# tetris_big_noregulator.net
KiCad netlist of a schematic drawn in EAGLE
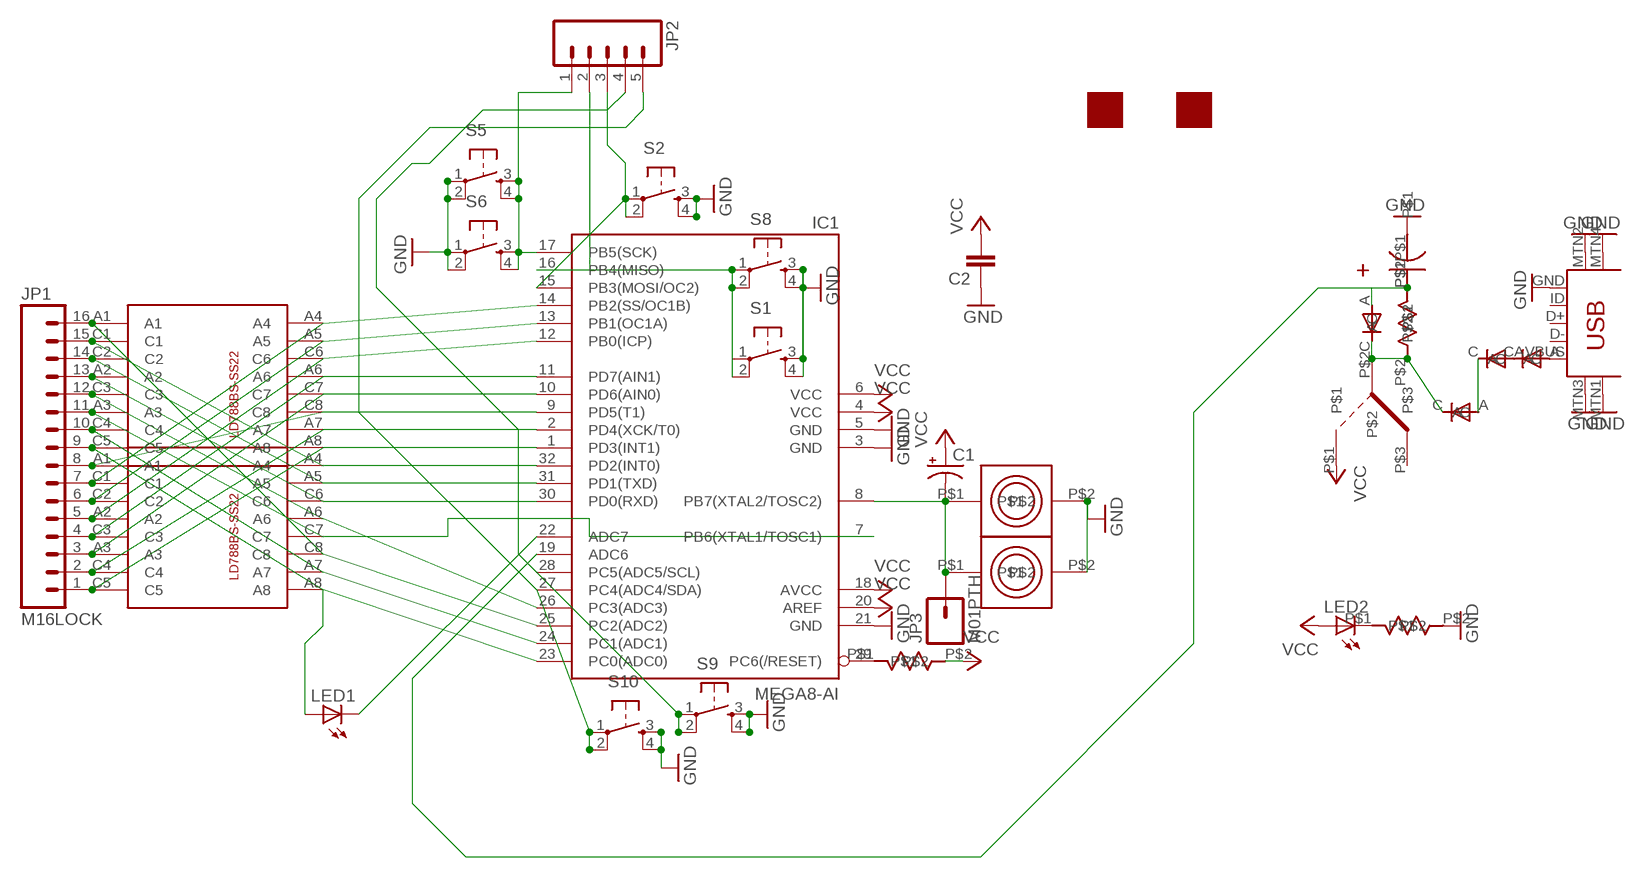
[diagram p0: schematic, sheet 1]

(export (version "E")
  (design (tool "Eeschema 10.0.6"))
  (components
    (comp (ref "C1")
      (value "CAP_POLPTH1")
      (footprint "eagle-import:CPOL-RADIAL-100UF-25V")
      (libsource (lib "eagle-import") (part "CAP_POLPTH1"))
    )
    (comp (ref "C2")
      (value "C-EU025-025X050")
      (footprint "eagle-import:C025-025X050")
      (libsource (lib "eagle-import") (part "C-EU025-025X050"))
    )
    (comp (ref "IC1")
      (value "MEGA8-AI")
      (footprint "eagle-import:TQFP32-08")
      (fields
        (field (name "MPN") "ATMEGA8-16AU")
        (field (name "MPN_1") "ATMEGA8-16AU")
        (field (name "OC_FARNELL") "9171371")
        (field (name "OC_NEWARK") "73M8863")
      )
      (libsource (lib "eagle-import") (part "MEGA8-AI"))
    )
    (comp (ref "JP1")
      (value "M16LOCK")
      (footprint "eagle-import:1X16_LOCK")
      (libsource (lib "eagle-import") (part "M16LOCK"))
    )
    (comp (ref "JP2")
      (value "M05LOCK")
      (footprint "eagle-import:1X05_LOCK")
      (libsource (lib "eagle-import") (part "M05LOCK"))
    )
    (comp (ref "JP3")
      (value "M01PTH")
      (footprint "eagle-import:1X01")
      (libsource (lib "eagle-import") (part "M01PTH"))
    )
    (comp (ref "LED1")
      (value "LED3MM")
      (footprint "eagle-import:LED3MM")
      (libsource (lib "eagle-import") (part "LED3MM"))
    )
    (comp (ref "LED2")
      (value "LED3MM")
      (footprint "eagle-import:LED3MM")
      (libsource (lib "eagle-import") (part "LED3MM"))
    )
    (comp (ref "S1")
      (value "TAC_SWITCHPTH")
      (footprint "eagle-import:TACTILE-PTH")
      (libsource (lib "eagle-import") (part "TAC_SWITCHPTH"))
    )
    (comp (ref "S2")
      (value "TAC_SWITCHPTH")
      (footprint "eagle-import:TACTILE-PTH")
      (libsource (lib "eagle-import") (part "TAC_SWITCHPTH"))
    )
    (comp (ref "S5")
      (value "TAC_SWITCHPTH")
      (footprint "eagle-import:TACTILE-PTH")
      (libsource (lib "eagle-import") (part "TAC_SWITCHPTH"))
    )
    (comp (ref "S6")
      (value "TAC_SWITCHPTH")
      (footprint "eagle-import:TACTILE-PTH")
      (libsource (lib "eagle-import") (part "TAC_SWITCHPTH"))
    )
    (comp (ref "S8")
      (value "TAC_SWITCHPTH")
      (footprint "eagle-import:TACTILE-PTH")
      (libsource (lib "eagle-import") (part "TAC_SWITCHPTH"))
    )
    (comp (ref "S9")
      (value "TAC_SWITCHPTH")
      (footprint "eagle-import:TACTILE-PTH")
      (libsource (lib "eagle-import") (part "TAC_SWITCHPTH"))
    )
    (comp (ref "S10")
      (value "TAC_SWITCHPTH")
      (footprint "eagle-import:TACTILE-PTH")
      (libsource (lib "eagle-import") (part "TAC_SWITCHPTH"))
    )
    (comp (ref "U$1")
      (value "LD-1088BS")
      (footprint "eagle-import:LD-1088BS")
      (libsource (lib "eagle-import") (part "LD-1088BS"))
    )
    (comp (ref "U$2")
      (value "LD-1088BS")
      (footprint "eagle-import:LD-1088BS")
      (libsource (lib "eagle-import") (part "LD-1088BS"))
    )
    (comp (ref "U$3")
      (value "LOGO")
      (footprint "eagle-import:LOGO")
      (libsource (lib "eagle-import") (part "LOGO"))
    )
    (comp (ref "U$4")
      (value "I-80450RF")
      (footprint "eagle-import:ISK4.1K_I-80450RF_I2G")
      (libsource (lib "eagle-import") (part "I-80450RF"))
    )
    (comp (ref "U$5")
      (value "NICHICON_12F")
      (footprint "eagle-import:NICHICON_10X30")
      (libsource (lib "eagle-import") (part "NICHICON_12F"))
    )
    (comp (ref "U$6")
      (value "LOGO")
      (footprint "eagle-import:LOGO")
      (libsource (lib "eagle-import") (part "LOGO"))
    )
    (comp (ref "U$7")
      (value "PIEZO_ROUND_PTH")
      (footprint "eagle-import:PIEZO_ROUND_ENCASED_PTH")
      (libsource (lib "eagle-import") (part "PIEZO_ROUND_PTH"))
    )
    (comp (ref "U$8")
      (value "R-7")
      (footprint "eagle-import:R-7")
      (libsource (lib "eagle-import") (part "R-7"))
    )
    (comp (ref "U$9")
      (value "SPST_BIG_PTH")
      (footprint "eagle-import:SWITCH_BIG")
      (libsource (lib "eagle-import") (part "SPST_BIG_PTH"))
    )
    (comp (ref "U$10")
      (value "R-7")
      (footprint "eagle-import:R-7")
      (libsource (lib "eagle-import") (part "R-7"))
    )
    (comp (ref "U$11")
      (value "R-7")
      (footprint "eagle-import:R-7")
      (libsource (lib "eagle-import") (part "R-7"))
    )
    (comp (ref "U$13")
      (value "D-6")
      (footprint "eagle-import:D-7.5")
      (libsource (lib "eagle-import") (part "D-6"))
    )
    (comp (ref "U$14")
      (value "D-6")
      (footprint "eagle-import:D-7.5")
      (libsource (lib "eagle-import") (part "D-6"))
    )
    (comp (ref "U$15")
      (value "D-6")
      (footprint "eagle-import:D-7.5")
      (libsource (lib "eagle-import") (part "D-6"))
    )
    (comp (ref "U$16")
      (value "D-6")
      (footprint "eagle-import:D-7.5")
      (libsource (lib "eagle-import") (part "D-6"))
    )
    (comp (ref "X1")
      (value "USB-MINIB-5PIN")
      (footprint "eagle-import:USB-MINIB")
      (libsource (lib "eagle-import") (part "USB-MINIB-5PIN"))
    )
  )
  (nets
    (net (code "1") (name "GND") (class "Default")
      (node (ref "C2") (pin "1") (pinfunction "1_1") (pintype "passive"))
      (node (ref "IC1") (pin "21") (pinfunction "GND_21") (pintype "power_in"))
      (node (ref "IC1") (pin "3") (pinfunction "GND_3") (pintype "power_in"))
      (node (ref "IC1") (pin "5") (pinfunction "GND_5") (pintype "power_in"))
      (node (ref "S1") (pin "3") (pinfunction "3_3") (pintype "passive"))
      (node (ref "S1") (pin "4") (pinfunction "4_4") (pintype "passive"))
      (node (ref "S10") (pin "3") (pinfunction "3_3") (pintype "passive"))
      (node (ref "S10") (pin "4") (pinfunction "4_4") (pintype "passive"))
      (node (ref "S2") (pin "3") (pinfunction "3_3") (pintype "passive"))
      (node (ref "S2") (pin "4") (pinfunction "4_4") (pintype "passive"))
      (node (ref "S5") (pin "1") (pinfunction "1_1") (pintype "passive"))
      (node (ref "S5") (pin "2") (pinfunction "2_2") (pintype "passive"))
      (node (ref "S6") (pin "1") (pinfunction "1_1") (pintype "passive"))
      (node (ref "S6") (pin "2") (pinfunction "2_2") (pintype "passive"))
      (node (ref "S8") (pin "3") (pinfunction "3_3") (pintype "passive"))
      (node (ref "S8") (pin "4") (pinfunction "4_4") (pintype "passive"))
      (node (ref "S9") (pin "3") (pinfunction "3_3") (pintype "passive"))
      (node (ref "S9") (pin "4") (pinfunction "4_4") (pintype "passive"))
      (node (ref "U$11") (pin "P$2") (pinfunction "P$2_P$2") (pintype "bidirectional"))
      (node (ref "U$4") (pin "P$2") (pinfunction "P$2_P$2") (pintype "bidirectional"))
      (node (ref "U$5") (pin "P$1") (pinfunction "P$1_P$1") (pintype "bidirectional"))
      (node (ref "U$7") (pin "P$2") (pinfunction "P$2_P$2") (pintype "bidirectional"))
      (node (ref "X1") (pin "GND") (pinfunction "GND_GND") (pintype "bidirectional"))
      (node (ref "X1") (pin "MTN1") (pinfunction "MTN2_MTN1") (pintype "bidirectional"))
      (node (ref "X1") (pin "MTN2") (pinfunction "MTN3_MTN2") (pintype "bidirectional"))
      (node (ref "X1") (pin "MTN3") (pinfunction "MTN1_MTN3") (pintype "bidirectional"))
      (node (ref "X1") (pin "MTN4") (pinfunction "MTN4_MTN4") (pintype "bidirectional"))
    )
    (net (code "2") (name "Net-(C1--)") (class "Default")
      (node (ref "C1") (pin "2") (pinfunction "-_2") (pintype "passive"))
      (node (ref "IC1") (pin "8") (pinfunction "PB7(XTAL2/TOSC2)_8") (pintype "bidirectional"))
      (node (ref "JP3") (pin "1") (pinfunction "1_1") (pintype "passive"))
      (node (ref "U$4") (pin "P$1") (pinfunction "P$1_P$1") (pintype "bidirectional"))
      (node (ref "U$7") (pin "P$1") (pinfunction "P$1_P$1") (pintype "bidirectional"))
    )
    (net (code "3") (name "Net-(IC1-ADC6)") (class "Default")
      (node (ref "IC1") (pin "19") (pinfunction "ADC6_19") (pintype "bidirectional"))
      (node (ref "U$16") (pin "A") (pinfunction "A_A") (pintype "bidirectional"))
      (node (ref "U$5") (pin "P$2") (pinfunction "P$2_P$2") (pintype "bidirectional"))
      (node (ref "U$8") (pin "P$1") (pinfunction "P$1_P$1") (pintype "bidirectional"))
    )
    (net (code "4") (name "Net-(IC1-ADC7)") (class "Default")
      (node (ref "IC1") (pin "22") (pinfunction "ADC7_22") (pintype "bidirectional"))
      (node (ref "LED1") (pin "K") (pinfunction "C_K") (pintype "passive"))
    )
    (net (code "5") (name "Net-(IC1-PB0(ICP))") (class "Default")
      (node (ref "IC1") (pin "12") (pinfunction "PB0(ICP)_12") (pintype "bidirectional"))
      (node (ref "JP1") (pin "5") (pinfunction "5_5") (pintype "passive"))
      (node (ref "U$1") (pin "A2") (pinfunction "A2_A2") (pintype "bidirectional"))
      (node (ref "U$2") (pin "C6") (pinfunction "C6_C6") (pintype "bidirectional"))
    )
    (net (code "6") (name "Net-(IC1-PB1(OC1A))") (class "Default")
      (node (ref "IC1") (pin "13") (pinfunction "PB1(OC1A)_13") (pintype "bidirectional"))
      (node (ref "JP1") (pin "6") (pinfunction "6_6") (pintype "passive"))
      (node (ref "U$1") (pin "C2") (pinfunction "C2_C2") (pintype "bidirectional"))
      (node (ref "U$2") (pin "A5") (pinfunction "A5_A5") (pintype "bidirectional"))
    )
    (net (code "7") (name "Net-(IC1-PB2(SS{slash}OC1B))") (class "Default")
      (node (ref "IC1") (pin "14") (pinfunction "PB2(SS/OC1B)_14") (pintype "bidirectional"))
      (node (ref "JP1") (pin "7") (pinfunction "7_7") (pintype "passive"))
      (node (ref "U$1") (pin "C1") (pinfunction "C1_C1") (pintype "bidirectional"))
      (node (ref "U$2") (pin "A4") (pinfunction "A4_A4") (pintype "bidirectional"))
    )
    (net (code "8") (name "Net-(IC1-PB3(MOSI{slash}OC2))") (class "Default")
      (node (ref "IC1") (pin "15") (pinfunction "PB3(MOSI/OC2)_15") (pintype "bidirectional"))
      (node (ref "JP2") (pin "3") (pinfunction "3_3") (pintype "passive"))
      (node (ref "S2") (pin "1") (pinfunction "1_1") (pintype "passive"))
      (node (ref "S2") (pin "2") (pinfunction "2_2") (pintype "passive"))
    )
    (net (code "9") (name "Net-(IC1-PB4(MISO))") (class "Default")
      (node (ref "IC1") (pin "16") (pinfunction "PB4(MISO)_16") (pintype "bidirectional"))
      (node (ref "JP2") (pin "2") (pinfunction "2_2") (pintype "passive"))
      (node (ref "S1") (pin "1") (pinfunction "1_1") (pintype "passive"))
      (node (ref "S1") (pin "2") (pinfunction "2_2") (pintype "passive"))
      (node (ref "S8") (pin "1") (pinfunction "1_1") (pintype "passive"))
      (node (ref "S8") (pin "2") (pinfunction "2_2") (pintype "passive"))
    )
    (net (code "10") (name "Net-(IC1-PB5(SCK))") (class "Default")
      (node (ref "IC1") (pin "17") (pinfunction "PB5(SCK)_17") (pintype "bidirectional"))
      (node (ref "JP2") (pin "1") (pinfunction "1_1") (pintype "passive"))
      (node (ref "S5") (pin "3") (pinfunction "3_3") (pintype "passive"))
      (node (ref "S5") (pin "4") (pinfunction "4_4") (pintype "passive"))
      (node (ref "S6") (pin "3") (pinfunction "3_3") (pintype "passive"))
      (node (ref "S6") (pin "4") (pinfunction "4_4") (pintype "passive"))
    )
    (net (code "11") (name "Net-(IC1-PB6(XTAL1{slash}TOSC1))") (class "Default")
      (node (ref "IC1") (pin "7") (pinfunction "PB6(XTAL1/TOSC1)_7") (pintype "bidirectional"))
      (node (ref "JP1") (pin "11") (pinfunction "11_11") (pintype "passive"))
      (node (ref "U$1") (pin "C7") (pinfunction "C7_C7") (pintype "bidirectional"))
      (node (ref "U$2") (pin "A3") (pinfunction "A3_A3") (pintype "bidirectional"))
    )
    (net (code "12") (name "Net-(IC1-PC0(ADC0))") (class "Default")
      (node (ref "IC1") (pin "23") (pinfunction "PC0(ADC0)_23") (pintype "bidirectional"))
      (node (ref "JP1") (pin "9") (pinfunction "9_9") (pintype "passive"))
      (node (ref "LED1") (pin "A") (pinfunction "A_A") (pintype "passive"))
      (node (ref "U$1") (pin "A8") (pinfunction "A8_A8") (pintype "bidirectional"))
      (node (ref "U$2") (pin "C5") (pinfunction "C5_C5") (pintype "bidirectional"))
    )
    (net (code "13") (name "Net-(IC1-PC1(ADC1))") (class "Default")
      (node (ref "IC1") (pin "24") (pinfunction "PC1(ADC1)_24") (pintype "bidirectional"))
      (node (ref "JP1") (pin "10") (pinfunction "10_10") (pintype "passive"))
      (node (ref "U$1") (pin "A7") (pinfunction "A7_A7") (pintype "bidirectional"))
      (node (ref "U$2") (pin "C4") (pinfunction "C4_C4") (pintype "bidirectional"))
    )
    (net (code "14") (name "Net-(IC1-PC2(ADC2))") (class "Default")
      (node (ref "IC1") (pin "25") (pinfunction "PC2(ADC2)_25") (pintype "bidirectional"))
      (node (ref "JP1") (pin "16") (pinfunction "16_16") (pintype "passive"))
      (node (ref "U$1") (pin "C8") (pinfunction "C8_C8") (pintype "bidirectional"))
      (node (ref "U$2") (pin "A1") (pinfunction "A1_A1") (pintype "bidirectional"))
    )
    (net (code "15") (name "Net-(IC1-PC3(ADC3))") (class "Default")
      (node (ref "IC1") (pin "26") (pinfunction "PC3(ADC3)_26") (pintype "bidirectional"))
      (node (ref "JP1") (pin "12") (pinfunction "12_12") (pintype "passive"))
      (node (ref "U$1") (pin "A6") (pinfunction "A6_A6") (pintype "bidirectional"))
      (node (ref "U$2") (pin "C3") (pinfunction "C3_C3") (pintype "bidirectional"))
    )
    (net (code "16") (name "Net-(IC1-PC4(ADC4{slash}SDA))") (class "Default")
      (node (ref "IC1") (pin "27") (pinfunction "PC4(ADC4/SDA)_27") (pintype "bidirectional"))
      (node (ref "JP2") (pin "5") (pinfunction "5_5") (pintype "passive"))
      (node (ref "S10") (pin "1") (pinfunction "1_1") (pintype "passive"))
      (node (ref "S10") (pin "2") (pinfunction "2_2") (pintype "passive"))
    )
    (net (code "17") (name "Net-(IC1-PC5(ADC5{slash}SCL))") (class "Default")
      (node (ref "IC1") (pin "28") (pinfunction "PC5(ADC5/SCL)_28") (pintype "bidirectional"))
      (node (ref "JP2") (pin "4") (pinfunction "4_4") (pintype "passive"))
      (node (ref "S9") (pin "1") (pinfunction "1_1") (pintype "passive"))
      (node (ref "S9") (pin "2") (pinfunction "2_2") (pintype "passive"))
    )
    (net (code "18") (name "Net-(IC1-PC6({slash}RESET))") (class "Default")
      (node (ref "IC1") (pin "29") (pinfunction "PC6(/RESET)_29") (pintype "bidirectional"))
      (node (ref "U$10") (pin "P$1") (pinfunction "P$1_P$1") (pintype "bidirectional"))
    )
    (net (code "19") (name "Net-(IC1-PD0(RXD))") (class "Default")
      (node (ref "IC1") (pin "30") (pinfunction "PD0(RXD)_30") (pintype "bidirectional"))
      (node (ref "JP1") (pin "13") (pinfunction "13_13") (pintype "passive"))
      (node (ref "U$1") (pin "C6") (pinfunction "C6_C6") (pintype "bidirectional"))
      (node (ref "U$2") (pin "A2") (pinfunction "A2_A2") (pintype "bidirectional"))
    )
    (net (code "20") (name "Net-(IC1-PD1(TXD))") (class "Default")
      (node (ref "IC1") (pin "31") (pinfunction "PD1(TXD)_31") (pintype "bidirectional"))
      (node (ref "JP1") (pin "14") (pinfunction "14_14") (pintype "passive"))
      (node (ref "U$1") (pin "A5") (pinfunction "A5_A5") (pintype "bidirectional"))
      (node (ref "U$2") (pin "C2") (pinfunction "C2_C2") (pintype "bidirectional"))
    )
    (net (code "21") (name "Net-(IC1-PD2(INT0))") (class "Default")
      (node (ref "IC1") (pin "32") (pinfunction "PD2(INT0)_32") (pintype "bidirectional"))
      (node (ref "JP1") (pin "15") (pinfunction "15_15") (pintype "passive"))
      (node (ref "U$1") (pin "A4") (pinfunction "A4_A4") (pintype "bidirectional"))
      (node (ref "U$2") (pin "C1") (pinfunction "C1_C1") (pintype "bidirectional"))
    )
    (net (code "22") (name "Net-(IC1-PD3(INT1))") (class "Default")
      (node (ref "IC1") (pin "1") (pinfunction "PD3(INT1)_1") (pintype "bidirectional"))
      (node (ref "JP1") (pin "1") (pinfunction "1_1") (pintype "passive"))
      (node (ref "U$1") (pin "C5") (pinfunction "C5_C5") (pintype "bidirectional"))
      (node (ref "U$2") (pin "A8") (pinfunction "A8_A8") (pintype "bidirectional"))
    )
    (net (code "23") (name "Net-(IC1-PD4(XCK{slash}T0))") (class "Default")
      (node (ref "IC1") (pin "2") (pinfunction "PD4(XCK/T0)_2") (pintype "bidirectional"))
      (node (ref "JP1") (pin "2") (pinfunction "2_2") (pintype "passive"))
      (node (ref "U$1") (pin "C4") (pinfunction "C4_C4") (pintype "bidirectional"))
      (node (ref "U$2") (pin "A7") (pinfunction "A7_A7") (pintype "bidirectional"))
    )
    (net (code "24") (name "Net-(IC1-PD5(T1))") (class "Default")
      (node (ref "IC1") (pin "9") (pinfunction "PD5(T1)_9") (pintype "bidirectional"))
      (node (ref "JP1") (pin "8") (pinfunction "8_8") (pintype "passive"))
      (node (ref "U$1") (pin "A1") (pinfunction "A1_A1") (pintype "bidirectional"))
      (node (ref "U$2") (pin "C8") (pinfunction "C8_C8") (pintype "bidirectional"))
    )
    (net (code "25") (name "Net-(IC1-PD6(AIN0))") (class "Default")
      (node (ref "IC1") (pin "10") (pinfunction "PD6(AIN0)_10") (pintype "bidirectional"))
      (node (ref "JP1") (pin "3") (pinfunction "3_3") (pintype "passive"))
      (node (ref "U$1") (pin "A3") (pinfunction "A3_A3") (pintype "bidirectional"))
      (node (ref "U$2") (pin "C7") (pinfunction "C7_C7") (pintype "bidirectional"))
    )
    (net (code "26") (name "Net-(IC1-PD7(AIN1))") (class "Default")
      (node (ref "IC1") (pin "11") (pinfunction "PD7(AIN1)_11") (pintype "bidirectional"))
      (node (ref "JP1") (pin "4") (pinfunction "4_4") (pintype "passive"))
      (node (ref "U$1") (pin "C3") (pinfunction "C3_C3") (pintype "bidirectional"))
      (node (ref "U$2") (pin "A6") (pinfunction "A6_A6") (pintype "bidirectional"))
    )
    (net (code "27") (name "Net-(LED2-C)") (class "Default")
      (node (ref "LED2") (pin "K") (pinfunction "C_K") (pintype "passive"))
      (node (ref "U$11") (pin "P$1") (pinfunction "P$1_P$1") (pintype "bidirectional"))
    )
    (net (code "28") (name "Net-(U$13-PadA)") (class "Default")
      (node (ref "U$13") (pin "A") (pinfunction "A_A") (pintype "bidirectional"))
      (node (ref "U$14") (pin "C") (pinfunction "C_C") (pintype "bidirectional"))
    )
    (net (code "29") (name "Net-(U$13-PadC)") (class "Default")
      (node (ref "U$13") (pin "C") (pinfunction "C_C") (pintype "bidirectional"))
      (node (ref "U$16") (pin "C") (pinfunction "C_C") (pintype "bidirectional"))
      (node (ref "U$8") (pin "P$2") (pinfunction "P$2_P$2") (pintype "bidirectional"))
      (node (ref "U$9") (pin "P$2") (pinfunction "P$2_P$2") (pintype "bidirectional"))
    )
    (net (code "30") (name "Net-(U$14-PadA)") (class "Default")
      (node (ref "U$14") (pin "A") (pinfunction "A_A") (pintype "bidirectional"))
      (node (ref "U$15") (pin "C") (pinfunction "C_C") (pintype "bidirectional"))
    )
    (net (code "31") (name "Net-(U$15-PadA)") (class "Default")
      (node (ref "U$15") (pin "A") (pinfunction "A_A") (pintype "bidirectional"))
      (node (ref "X1") (pin "VBUS") (pinfunction "VBUS_VBUS") (pintype "bidirectional"))
    )
    (net (code "32") (name "VCC") (class "Default")
      (node (ref "C1") (pin "1") (pinfunction "+_1") (pintype "passive"))
      (node (ref "C2") (pin "2") (pinfunction "2_2") (pintype "passive"))
      (node (ref "IC1") (pin "18") (pinfunction "AVCC_18") (pintype "power_in"))
      (node (ref "IC1") (pin "20") (pinfunction "AREF_20") (pintype "passive"))
      (node (ref "IC1") (pin "4") (pinfunction "VCC_4") (pintype "power_in"))
      (node (ref "IC1") (pin "6") (pinfunction "VCC_6") (pintype "power_in"))
      (node (ref "LED2") (pin "A") (pinfunction "A_A") (pintype "passive"))
      (node (ref "U$10") (pin "P$2") (pinfunction "P$2_P$2") (pintype "bidirectional"))
      (node (ref "U$9") (pin "P$1") (pinfunction "P$1_P$1") (pintype "bidirectional"))
    )
    (net (code "33") (name "unconnected-(U$9-PadP$3)") (class "Default")
      (node (ref "U$9") (pin "P$3") (pinfunction "P$3_P$3") (pintype "bidirectional"))
    )
    (net (code "34") (name "unconnected-(X1-PadD+)") (class "Default")
      (node (ref "X1") (pin "D+") (pinfunction "D+_D+") (pintype "bidirectional"))
    )
    (net (code "35") (name "unconnected-(X1-PadD-)") (class "Default")
      (node (ref "X1") (pin "D-") (pinfunction "D-_D-") (pintype "bidirectional"))
    )
    (net (code "36") (name "unconnected-(X1-PadID)") (class "Default")
      (node (ref "X1") (pin "ID") (pinfunction "ID_ID") (pintype "bidirectional"))
    )
  )
)
